# JacdacCableExtender_38.net
KiCad netlist of a schematic drawn in Altium Designer
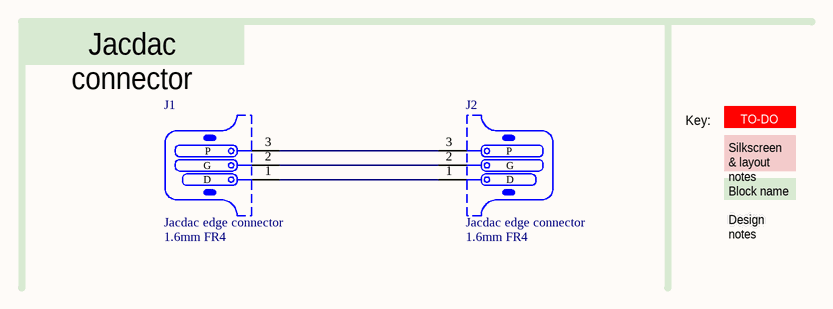
[diagram p0: JacdacCableExtender 38.SchDoc]

(export (version "E")
  (design (tool "Eeschema 10.0.6"))
  (components
    (comp (ref "J1")
      (value "Jacdac edge connector")
      (footprint "JACDAC_edge_connector:JACDAC_EDGE_CONNECTOR_0.2mm_T&G")
      (description "3 pin Jacdac edge connector 1.27mm pitch")
      (fields
        (field (name "MANUFACTURER PART NUMBER") "JACDAC_EDGE_CONNECTOR")
        (field (name "PCB TYPE") "1.6mm FR4")
        (field (name "CHECKED BY") "?")
        (field (name "CREATED BY") "D. Gakure")
      )
      (libsource (lib "generic-con") (part "Jacdac edge connector"))
    )
    (comp (ref "J2")
      (value "Jacdac edge connector")
      (footprint "JACDAC_edge_connector:JACDAC_EDGE_CONNECTOR_0.2mm_T&G")
      (description "3 pin Jacdac edge connector 1.27mm pitch")
      (fields
        (field (name "MANUFACTURER PART NUMBER") "JACDAC_EDGE_CONNECTOR")
        (field (name "PCB TYPE") "1.6mm FR4")
        (field (name "CHECKED BY") "?")
        (field (name "CREATED BY") "D. Gakure")
      )
      (libsource (lib "") (part "Jacdac edge connector_1"))
    )
  )
  (nets
    (net (code "1") (name "Net-(J1-D)") (class "Default")
      (node (ref "J1") (pin "1") (pinfunction "D_1") (pintype "passive"))
      (node (ref "J2") (pin "1") (pinfunction "D_1") (pintype "passive"))
    )
    (net (code "2") (name "Net-(J1-G)") (class "Default")
      (node (ref "J1") (pin "2") (pinfunction "G_2") (pintype "passive"))
      (node (ref "J2") (pin "2") (pinfunction "G_2") (pintype "passive"))
    )
    (net (code "3") (name "Net-(J1-P)") (class "Default")
      (node (ref "J1") (pin "3") (pinfunction "P_3") (pintype "passive"))
      (node (ref "J2") (pin "3") (pinfunction "P_3") (pintype "passive"))
    )
  )
)
